# Part25_Button_LED.net
KiCad netlist of a schematic drawn in Altium Designer
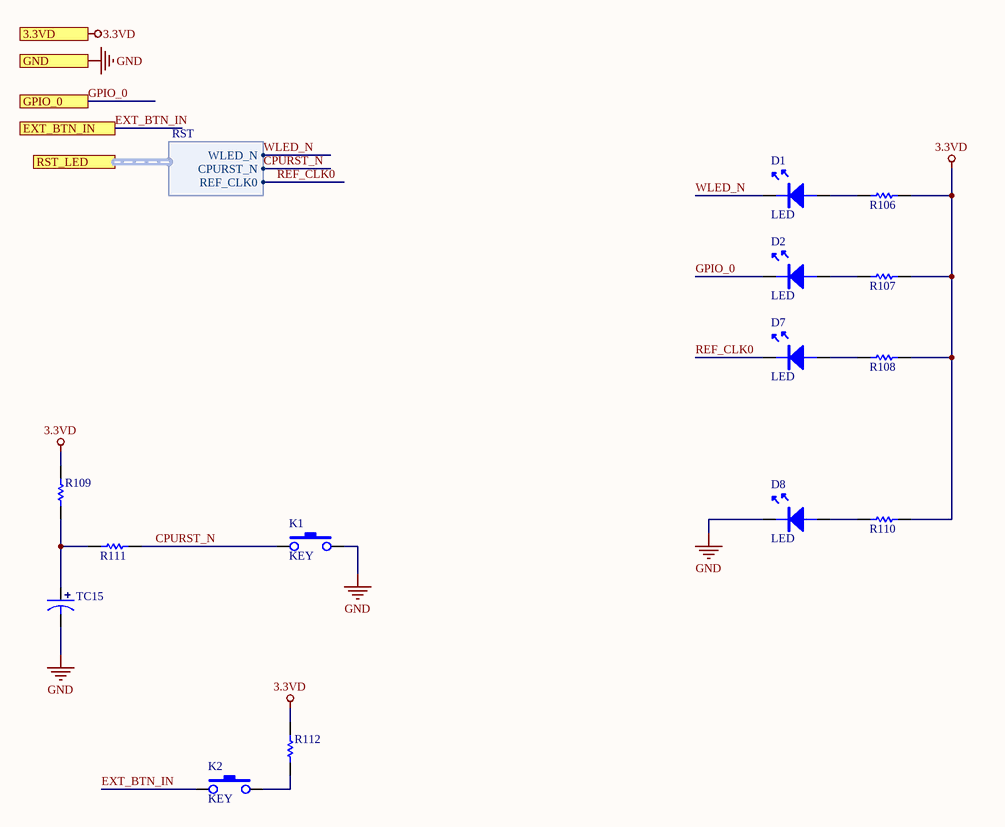
[diagram p0: Part25_Button_LED.SchDoc]

(export (version "E")
  (design (tool "Eeschema 10.0.6"))
  (components
    (comp (ref "D1") (value "LED") (footprint "LED-0603B") (libsource (lib "LED") (part "LED")))
    (comp (ref "D2") (value "LED") (footprint "LED-0603B") (libsource (lib "LED") (part "LED")))
    (comp (ref "D7") (value "LED") (footprint "LED-0603B") (libsource (lib "LED") (part "LED")))
    (comp (ref "D8") (value "LED") (footprint "LED-0603B") (libsource (lib "LED") (part "LED")))
    (comp (ref "K1") (value "KEY") (footprint "SMD-6X6X4.3") (libsource (lib "轻触开关") (part "KEY")))
    (comp (ref "K2") (value "KEY") (footprint "SMD-6X6X4.3") (libsource (lib "轻触开关") (part "KEY")))
    (comp (ref "R106") (value "RES") (footprint "0402R") (libsource (lib "电阻") (part "RES")))
    (comp (ref "R107") (value "RES") (footprint "0402R") (libsource (lib "电阻") (part "RES")))
    (comp (ref "R108") (value "RES") (footprint "0402R") (libsource (lib "电阻") (part "RES")))
    (comp (ref "R109") (value "RES") (footprint "0402R") (libsource (lib "电阻") (part "RES")))
    (comp (ref "R110") (value "RES") (footprint "0402R") (libsource (lib "电阻") (part "RES")))
    (comp (ref "R111") (value "RES") (footprint "0402R") (libsource (lib "电阻") (part "RES")))
    (comp (ref "R112") (value "RES") (footprint "0402R") (libsource (lib "电阻") (part "RES")))
    (comp (ref "TC15")
      (value "4.7uF/6.3V")
      (footprint "TAJ-A/3216")
      (description "钽电容")
      (libsource (lib "电容") (part "TCAP"))
    )
  )
  (nets
    (net (code "2") (name "/CPURST_N") (class "Default")
      (node (ref "K1") (pin "1") (pinfunction "1_1") (pintype "passive"))
      (node (ref "R111") (pin "2") (pinfunction "2_2") (pintype "passive"))
    )
    (net (code "3") (name "/EXT_BTN_IN") (class "Default")
      (node (ref "K2") (pin "1") (pinfunction "1_1") (pintype "passive"))
    )
    (net (code "4") (name "/GPIO_0") (class "Default")
      (node (ref "D2") (pin "K") (pinfunction "K_K") (pintype "passive"))
    )
    (net (code "5") (name "/REF_CLK0") (class "Default")
      (node (ref "D7") (pin "K") (pinfunction "K_K") (pintype "passive"))
    )
    (net (code "6") (name "/WLED_N") (class "Default")
      (node (ref "D1") (pin "K") (pinfunction "K_K") (pintype "passive"))
    )
    (net (code "8") (name "3.3VD") (class "Default")
      (node (ref "R106") (pin "2") (pinfunction "2_2") (pintype "passive"))
      (node (ref "R107") (pin "2") (pinfunction "2_2") (pintype "passive"))
      (node (ref "R108") (pin "2") (pinfunction "2_2") (pintype "passive"))
      (node (ref "R109") (pin "1") (pinfunction "1_1") (pintype "passive"))
      (node (ref "R110") (pin "2") (pinfunction "2_2") (pintype "passive"))
      (node (ref "R112") (pin "1") (pinfunction "1_1") (pintype "passive"))
    )
    (net (code "9") (name "GND") (class "Default")
      (node (ref "D8") (pin "K") (pinfunction "K_K") (pintype "passive"))
      (node (ref "K1") (pin "3") (pinfunction "3_3") (pintype "passive"))
      (node (ref "TC15") (pin "2") (pinfunction "2_2") (pintype "passive"))
    )
    (net (code "10") (name "Net-(D1-PadA)") (class "Default")
      (node (ref "D1") (pin "A") (pinfunction "A_A") (pintype "passive"))
      (node (ref "R106") (pin "1") (pinfunction "1_1") (pintype "passive"))
    )
    (net (code "11") (name "Net-(D2-PadA)") (class "Default")
      (node (ref "D2") (pin "A") (pinfunction "A_A") (pintype "passive"))
      (node (ref "R107") (pin "1") (pinfunction "1_1") (pintype "passive"))
    )
    (net (code "12") (name "Net-(D7-PadA)") (class "Default")
      (node (ref "D7") (pin "A") (pinfunction "A_A") (pintype "passive"))
      (node (ref "R108") (pin "1") (pinfunction "1_1") (pintype "passive"))
    )
    (net (code "13") (name "Net-(D8-PadA)") (class "Default")
      (node (ref "D8") (pin "A") (pinfunction "A_A") (pintype "passive"))
      (node (ref "R110") (pin "1") (pinfunction "1_1") (pintype "passive"))
    )
    (net (code "14") (name "Net-(K2-Pad3)") (class "Default")
      (node (ref "K2") (pin "3") (pinfunction "3_3") (pintype "passive"))
      (node (ref "R112") (pin "2") (pinfunction "2_2") (pintype "passive"))
    )
    (net (code "15") (name "Net-(R109-Pad2)") (class "Default")
      (node (ref "R109") (pin "2") (pinfunction "2_2") (pintype "passive"))
      (node (ref "R111") (pin "1") (pinfunction "1_1") (pintype "passive"))
      (node (ref "TC15") (pin "1") (pinfunction "1_1") (pintype "passive"))
    )
  )
)
